# X14-Distribution.net
KiCad netlist of a schematic drawn in EAGLE
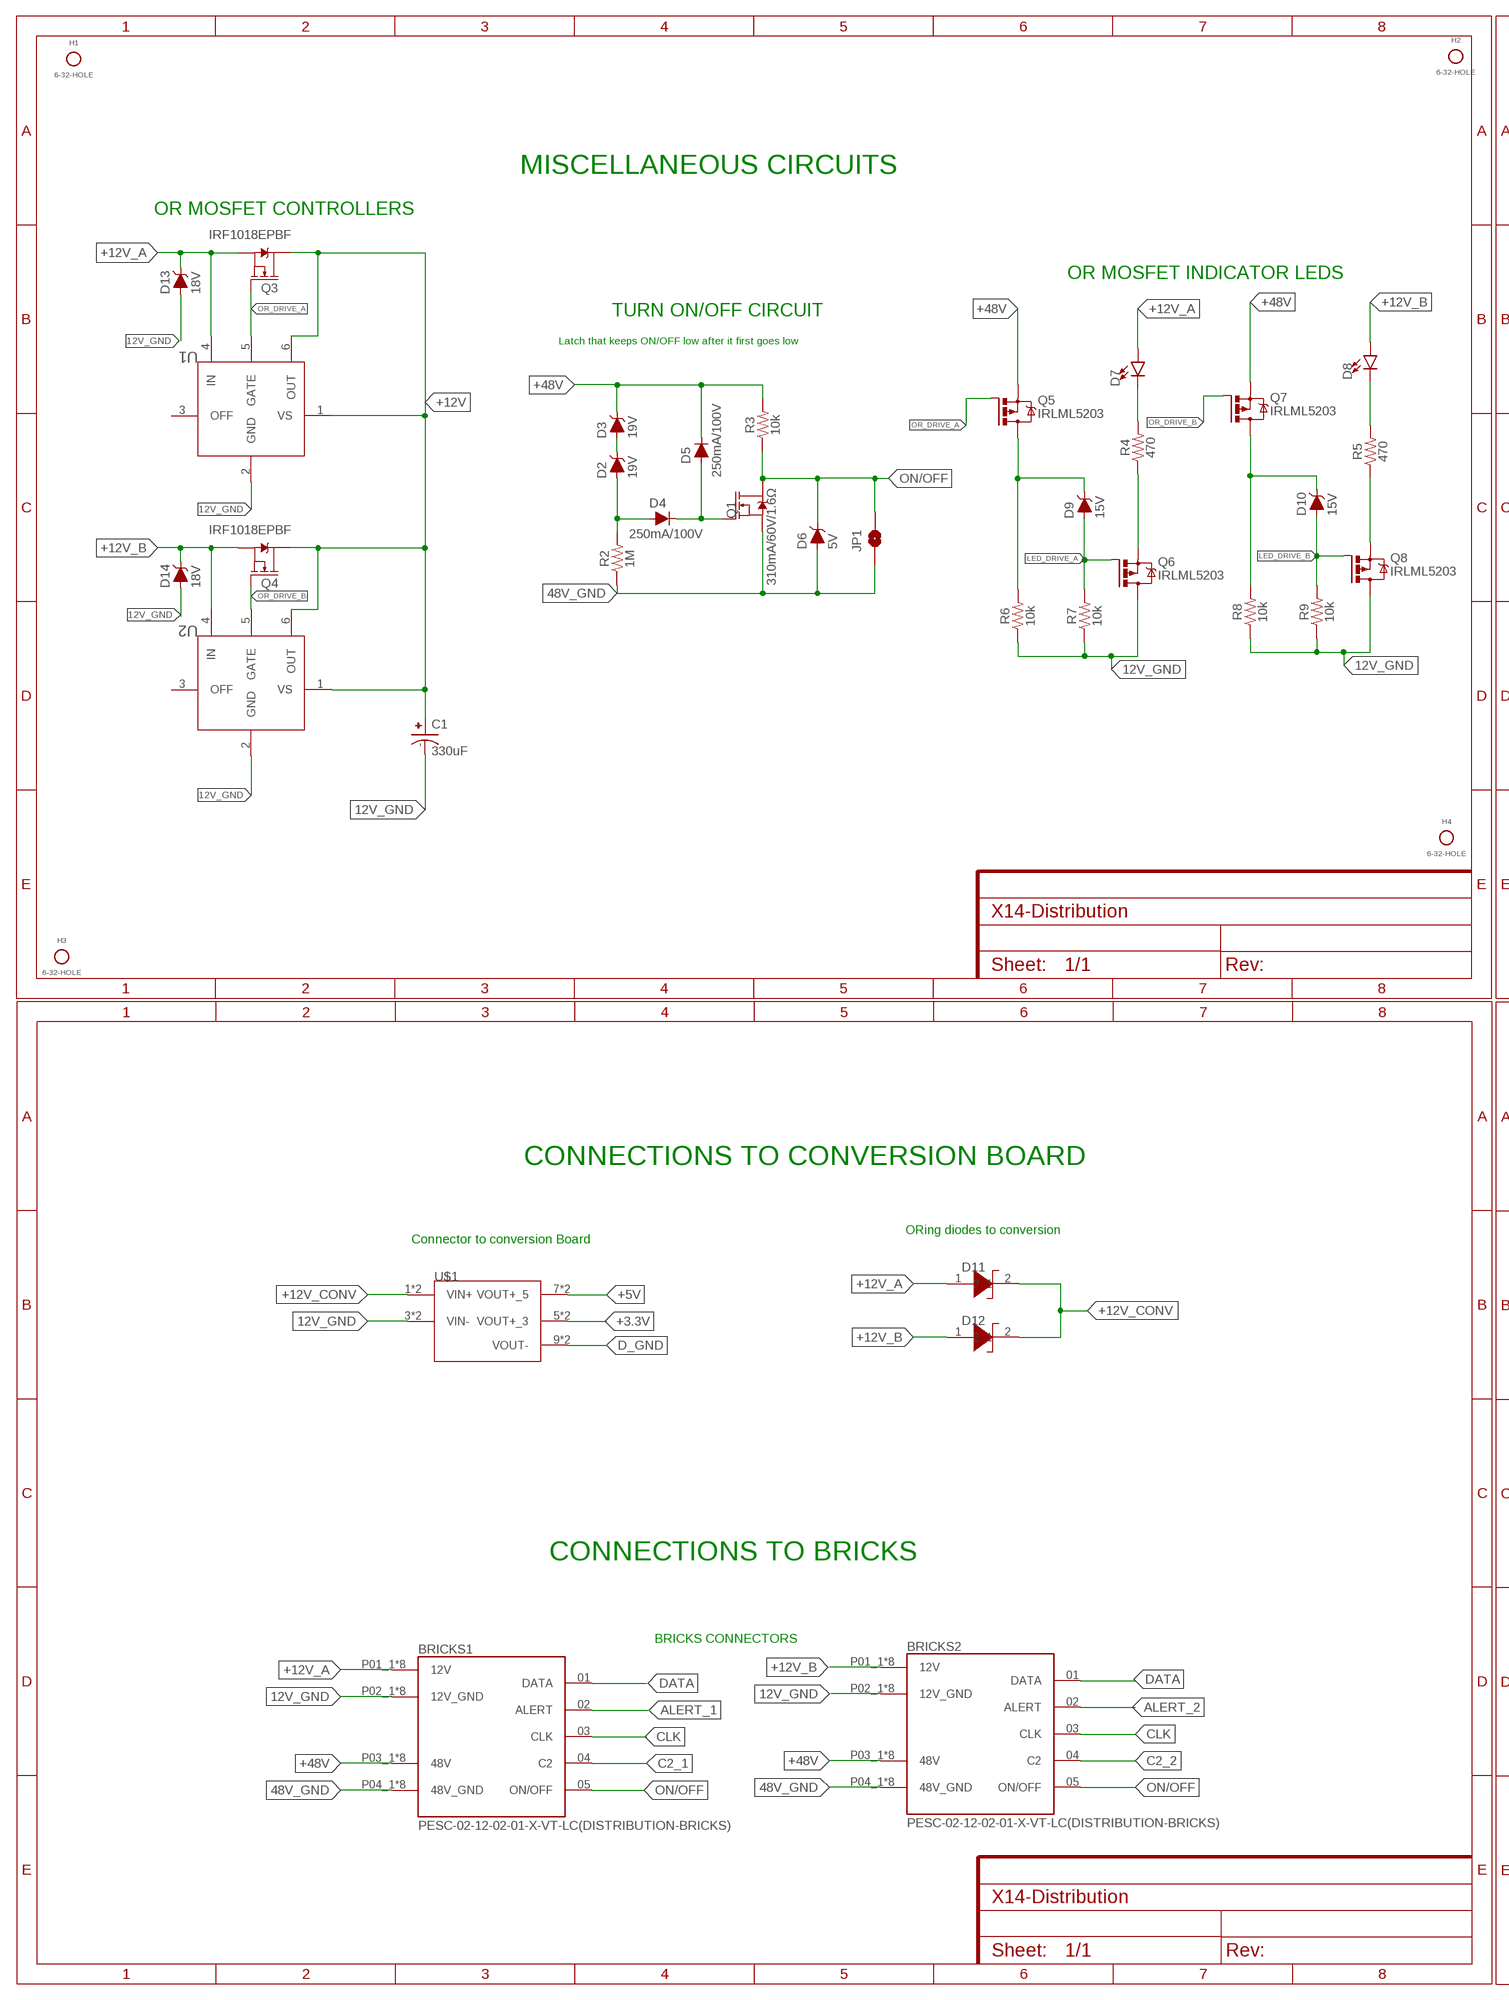
[diagram p0: schematic, sheet 1, part 1 of 2]
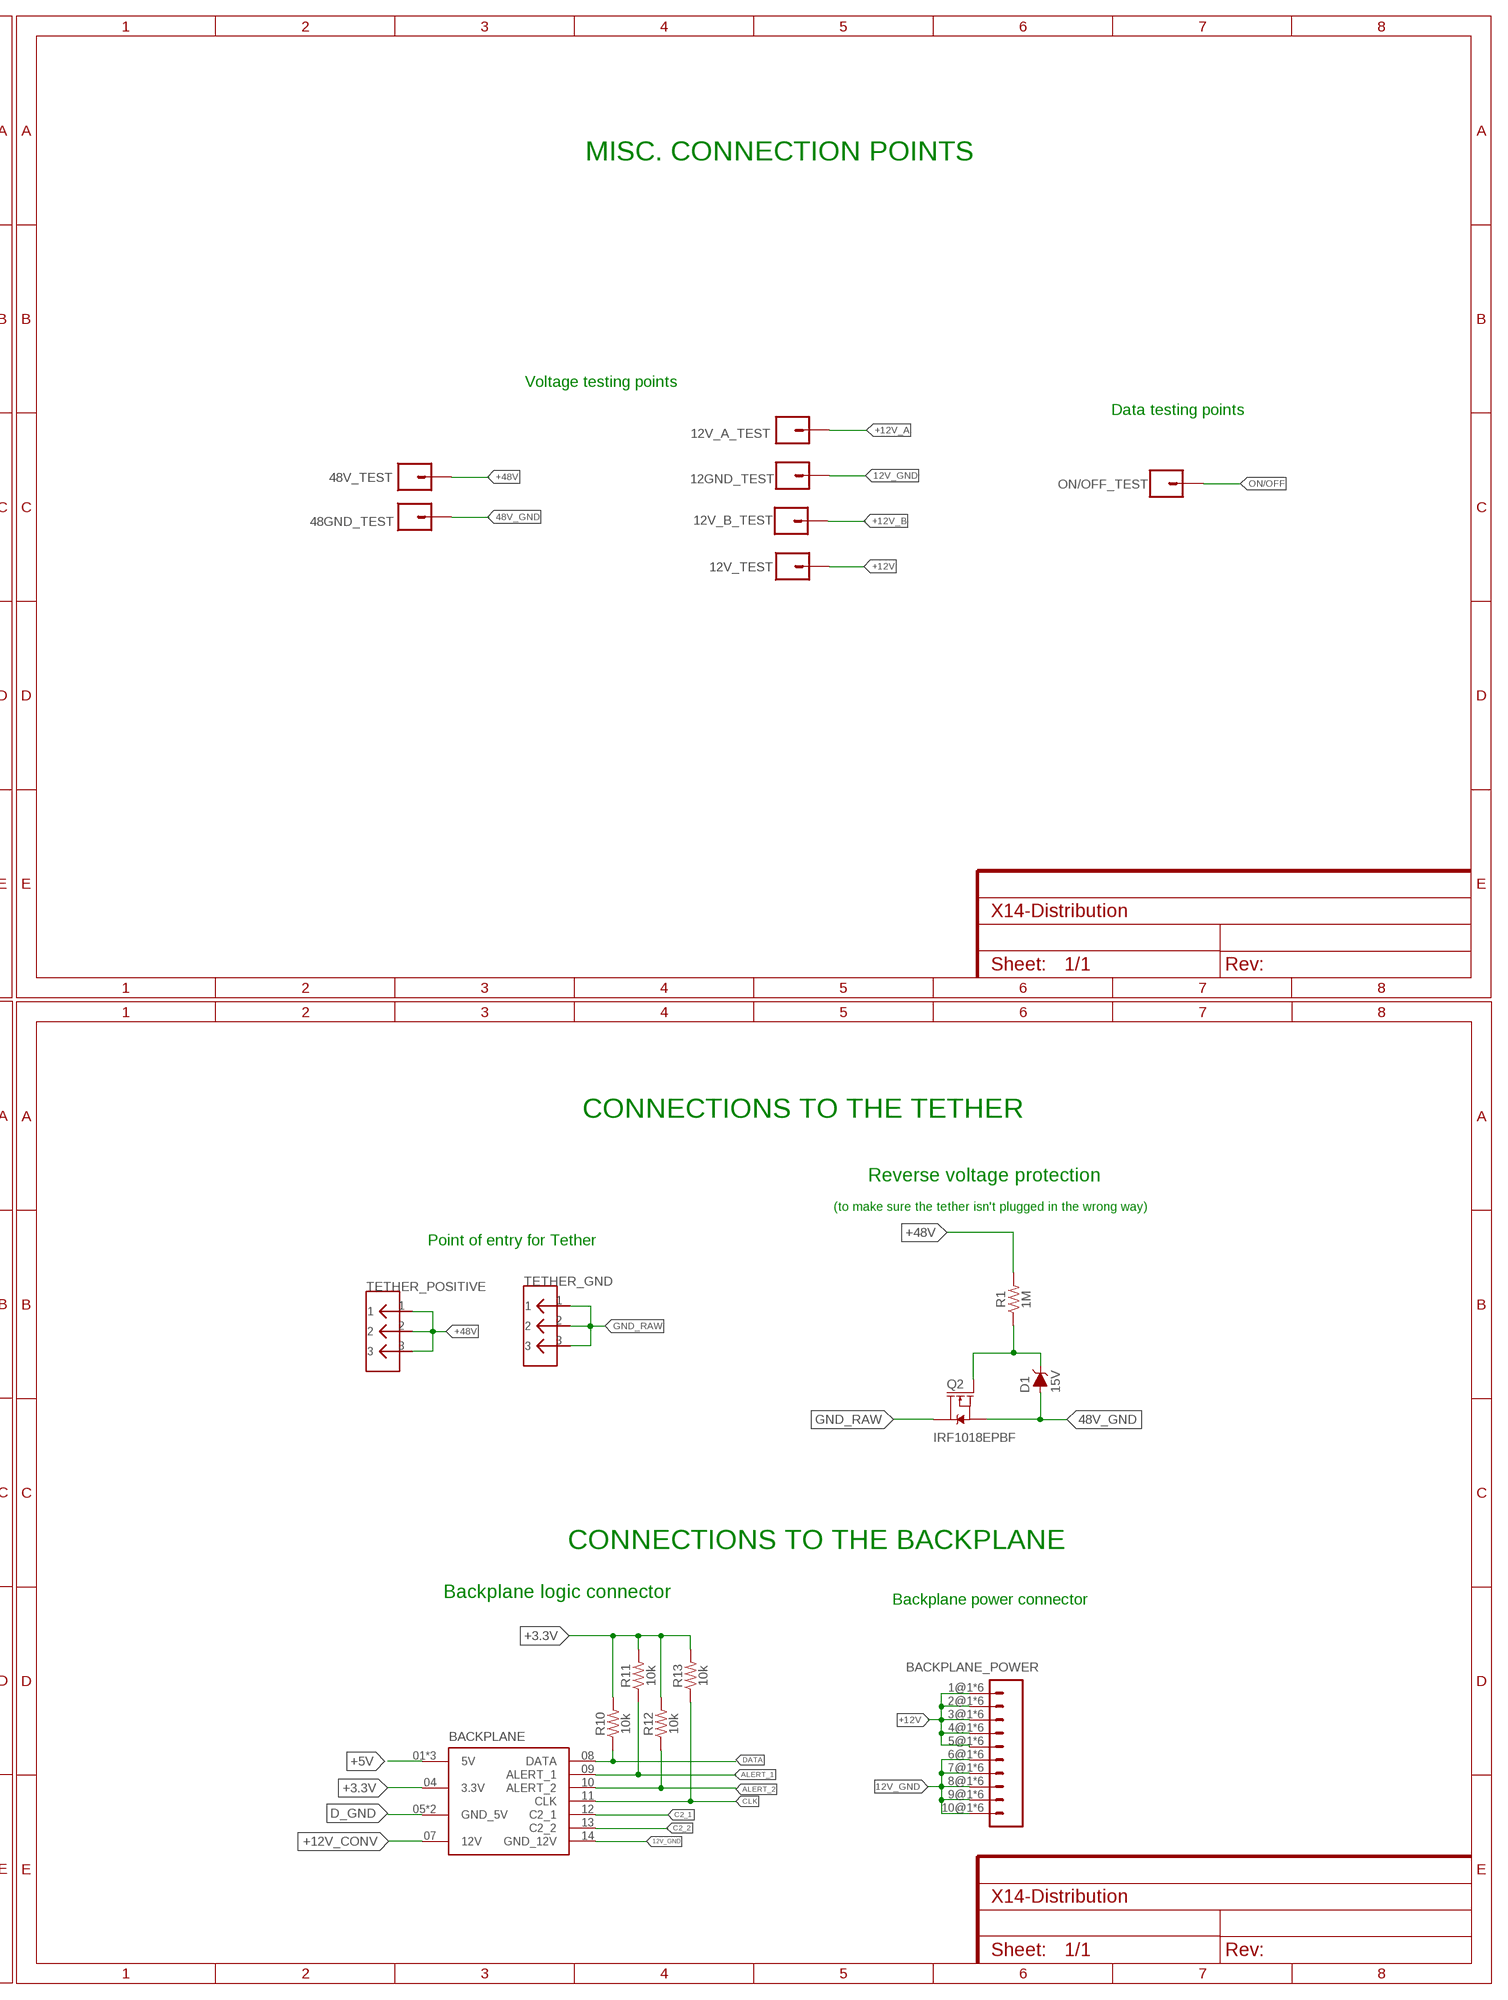
[diagram p1: schematic, sheet 1, part 2 of 2]

(export (version "E")
  (design (tool "Eeschema 10.0.6"))
  (components
    (comp (ref "12GND_TEST")
      (value "CONN_01")
      (footprint "eagle-import:1X01")
      (libsource (lib "eagle-import") (part "CONN_01"))
    )
    (comp (ref "12V_A_TEST")
      (value "CONN_01")
      (footprint "eagle-import:1X01")
      (libsource (lib "eagle-import") (part "CONN_01"))
    )
    (comp (ref "12V_B_TEST")
      (value "CONN_01")
      (footprint "eagle-import:1X01")
      (libsource (lib "eagle-import") (part "CONN_01"))
    )
    (comp (ref "12V_TEST")
      (value "CONN_01")
      (footprint "eagle-import:1X01")
      (libsource (lib "eagle-import") (part "CONN_01"))
    )
    (comp (ref "48GND_TEST")
      (value "CONN_01")
      (footprint "eagle-import:1X01")
      (libsource (lib "eagle-import") (part "CONN_01"))
    )
    (comp (ref "48V_TEST")
      (value "CONN_01")
      (footprint "eagle-import:1X01")
      (libsource (lib "eagle-import") (part "CONN_01"))
    )
    (comp (ref "BACKPLANE")
      (value "DISTRIBUTION-BACKPLANE")
      (footprint "eagle-import:SAMTEC_IPL1-107-01-X-D-K(D-B)")
      (libsource (lib "eagle-import") (part "DISTRIBUTION-BACKPLANE"))
    )
    (comp (ref "BACKPLANE_POWER")
      (value "MPPT-10-01-01-L-RA-SD")
      (footprint "eagle-import:MPPT-10-01-01-L-RA-SD")
      (libsource (lib "eagle-import") (part "MPPT-10-01-01-L-RA-SD"))
    )
    (comp (ref "BRICKS1")
      (value "PESC-02-12-02-01-X-VT-LC(DISTRIBUTION-BRICKS)")
      (footprint "eagle-import:SAMTEC_PESC-02-12-02-01-X-VT-LC(D-B)")
      (fields (field (name "MANUFACTURER") "Samtec"))
      (libsource (lib "eagle-import") (part "PESC-02-12-02-01-X-VT-LC(DISTRIBUTION-BRICKS)"))
    )
    (comp (ref "BRICKS2")
      (value "PESC-02-12-02-01-X-VT-LC(DISTRIBUTION-BRICKS)")
      (footprint "eagle-import:SAMTEC_PESC-02-12-02-01-X-VT-LC(D-B)")
      (fields (field (name "MANUFACTURER") "Samtec"))
      (libsource (lib "eagle-import") (part "PESC-02-12-02-01-X-VT-LC(DISTRIBUTION-BRICKS)"))
    )
    (comp (ref "C1")
      (value "330uF")
      (footprint "eagle-import:CAPAE1030X1050N")
      (fields
        (field (name "ARROW_PART_NUMBER") "UCM1H331MNL1GS")
        (field (name "MOUSER_PART_NUMBER") "647-UCM1H331MNL1GS")
      )
      (libsource (lib "eagle-import") (part "UCM1H331MNL1GS"))
    )
    (comp (ref "D1")
      (value "15V")
      (footprint "eagle-import:SOD-323")
      (libsource (lib "eagle-import") (part "DIODE-ZENER-BZT52C3V6S"))
    )
    (comp (ref "D2")
      (value "19V")
      (footprint "eagle-import:SOD-323")
      (libsource (lib "eagle-import") (part "DIODE-ZENER-BZT52C3V6S"))
    )
    (comp (ref "D3")
      (value "19V")
      (footprint "eagle-import:SOD-323")
      (libsource (lib "eagle-import") (part "DIODE-ZENER-BZT52C3V6S"))
    )
    (comp (ref "D4")
      (value "250mA/100V")
      (footprint "eagle-import:SOD-323")
      (libsource (lib "eagle-import") (part "DIODE-BAS16J"))
    )
    (comp (ref "D5")
      (value "250mA/100V")
      (footprint "eagle-import:SOD-323")
      (libsource (lib "eagle-import") (part "DIODE-BAS16J"))
    )
    (comp (ref "D6")
      (value "5V")
      (footprint "eagle-import:SOD-323")
      (libsource (lib "eagle-import") (part "DIODE-ZENER-BZT52C3V6S"))
    )
    (comp (ref "D7")
      (value "LED0603")
      (footprint "eagle-import:LED-0603")
      (libsource (lib "eagle-import") (part "LED0603"))
    )
    (comp (ref "D8")
      (value "LED0603")
      (footprint "eagle-import:LED-0603")
      (libsource (lib "eagle-import") (part "LED0603"))
    )
    (comp (ref "D9")
      (value "15V")
      (footprint "eagle-import:SOD-323")
      (libsource (lib "eagle-import") (part "DIODE-ZENER-BZT52C3V6S"))
    )
    (comp (ref "D10")
      (value "15V")
      (footprint "eagle-import:SOD-323")
      (libsource (lib "eagle-import") (part "DIODE-ZENER-BZT52C3V6S"))
    )
    (comp (ref "D11")
      (value "DIODE-DO-214AC(SK34ATR)")
      (footprint "eagle-import:DIODE-DO-214AC(SK34ATR)")
      (libsource (lib "eagle-import") (part "DIODE-DO-214AC(SK34ATR)"))
    )
    (comp (ref "D12")
      (value "DIODE-DO-214AC(SK34ATR)")
      (footprint "eagle-import:DIODE-DO-214AC(SK34ATR)")
      (libsource (lib "eagle-import") (part "DIODE-DO-214AC(SK34ATR)"))
    )
    (comp (ref "D13")
      (value "18V")
      (footprint "eagle-import:PANASONIC_SMINI2-F5-B")
      (libsource (lib "eagle-import") (part "DIODE-ZENER-DZ2J150M0L"))
    )
    (comp (ref "D14")
      (value "18V")
      (footprint "eagle-import:PANASONIC_SMINI2-F5-B")
      (libsource (lib "eagle-import") (part "DIODE-ZENER-DZ2J150M0L"))
    )
    (comp (ref "H1")
      (value "6-32-HOLE")
      (footprint "eagle-import:6-32-HOLE")
      (libsource (lib "eagle-import") (part "6-32-HOLE"))
    )
    (comp (ref "H2")
      (value "6-32-HOLE")
      (footprint "eagle-import:6-32-HOLE")
      (libsource (lib "eagle-import") (part "6-32-HOLE"))
    )
    (comp (ref "H3")
      (value "6-32-HOLE")
      (footprint "eagle-import:6-32-HOLE")
      (libsource (lib "eagle-import") (part "6-32-HOLE"))
    )
    (comp (ref "H4")
      (value "6-32-HOLE")
      (footprint "eagle-import:6-32-HOLE")
      (libsource (lib "eagle-import") (part "6-32-HOLE"))
    )
    (comp (ref "JP1")
      (value "JUMPER-SMT_2_NO_SILK")
      (footprint "eagle-import:SMT-JUMPER_2_NO_SILK")
      (libsource (lib "eagle-import") (part "JUMPER-SMT_2_NO_SILK"))
    )
    (comp (ref "ON/OFF_TEST")
      (value "CONN_01")
      (footprint "eagle-import:1X01")
      (libsource (lib "eagle-import") (part "CONN_01"))
    )
    (comp (ref "Q1")
      (value "310mA/60V/1.6Ω")
      (footprint "eagle-import:SOT323")
      (libsource (lib "eagle-import") (part "MOSFET-NCH-2N7002PW"))
    )
    (comp (ref "Q2")
      (value "IRF1018EPBF")
      (footprint "eagle-import:TO263")
      (libsource (lib "eagle-import") (part "IRF1018EPBF"))
    )
    (comp (ref "Q3")
      (value "IRF1018EPBF")
      (footprint "eagle-import:TO263")
      (libsource (lib "eagle-import") (part "IRF1018EPBF"))
    )
    (comp (ref "Q4")
      (value "IRF1018EPBF")
      (footprint "eagle-import:TO263")
      (libsource (lib "eagle-import") (part "IRF1018EPBF"))
    )
    (comp (ref "Q5")
      (value "IRLML5203")
      (footprint "eagle-import:SOT23")
      (fields (field (name "MANUFACTURER") "Infineon Technologies") (field (name "MPN") "IRLML5203TRPBF"))
      (libsource (lib "eagle-import") (part "PMOSFET_IRLML5203"))
    )
    (comp (ref "Q6")
      (value "IRLML5203")
      (footprint "eagle-import:SOT23")
      (fields (field (name "MANUFACTURER") "Infineon Technologies") (field (name "MPN") "IRLML5203TRPBF"))
      (libsource (lib "eagle-import") (part "PMOSFET_IRLML5203"))
    )
    (comp (ref "Q7")
      (value "IRLML5203")
      (footprint "eagle-import:SOT23")
      (fields (field (name "MANUFACTURER") "Infineon Technologies") (field (name "MPN") "IRLML5203TRPBF"))
      (libsource (lib "eagle-import") (part "PMOSFET_IRLML5203"))
    )
    (comp (ref "Q8")
      (value "IRLML5203")
      (footprint "eagle-import:SOT23")
      (fields (field (name "MANUFACTURER") "Infineon Technologies") (field (name "MPN") "IRLML5203TRPBF"))
      (libsource (lib "eagle-import") (part "PMOSFET_IRLML5203"))
    )
    (comp (ref "R1")
      (value "1M")
      (footprint "eagle-import:0603")
      (libsource (lib "eagle-import") (part "RESISTOR0603"))
    )
    (comp (ref "R2")
      (value "1M")
      (footprint "eagle-import:0603")
      (libsource (lib "eagle-import") (part "RESISTOR0603"))
    )
    (comp (ref "R3")
      (value "10k")
      (footprint "eagle-import:0603")
      (libsource (lib "eagle-import") (part "RESISTOR0603"))
    )
    (comp (ref "R4")
      (value "470")
      (footprint "eagle-import:0603")
      (libsource (lib "eagle-import") (part "RESISTOR0603"))
    )
    (comp (ref "R5")
      (value "470")
      (footprint "eagle-import:0603")
      (libsource (lib "eagle-import") (part "RESISTOR0603"))
    )
    (comp (ref "R6")
      (value "10k")
      (footprint "eagle-import:0603")
      (libsource (lib "eagle-import") (part "RESISTOR0603"))
    )
    (comp (ref "R7")
      (value "10k")
      (footprint "eagle-import:0603")
      (libsource (lib "eagle-import") (part "RESISTOR0603"))
    )
    (comp (ref "R8")
      (value "10k")
      (footprint "eagle-import:0603")
      (libsource (lib "eagle-import") (part "RESISTOR0603"))
    )
    (comp (ref "R9")
      (value "10k")
      (footprint "eagle-import:0603")
      (libsource (lib "eagle-import") (part "RESISTOR0603"))
    )
    (comp (ref "R10")
      (value "10k")
      (footprint "eagle-import:0603")
      (libsource (lib "eagle-import") (part "RESISTOR0603"))
    )
    (comp (ref "R11")
      (value "10k")
      (footprint "eagle-import:0603")
      (libsource (lib "eagle-import") (part "RESISTOR0603"))
    )
    (comp (ref "R12")
      (value "10k")
      (footprint "eagle-import:0603")
      (libsource (lib "eagle-import") (part "RESISTOR0603"))
    )
    (comp (ref "R13")
      (value "10k")
      (footprint "eagle-import:0603")
      (libsource (lib "eagle-import") (part "RESISTOR0603"))
    )
    (comp (ref "TETHER_GND")
      (value "796636-3")
      (footprint "eagle-import:796636-3")
      (libsource (lib "eagle-import") (part "796636-3"))
    )
    (comp (ref "TETHER_POSITIVE")
      (value "796636-3")
      (footprint "eagle-import:796636-3")
      (libsource (lib "eagle-import") (part "796636-3"))
    )
    (comp (ref "U$1")
      (value "DISTRIBUTION-CONVERSION")
      (footprint "eagle-import:TSW-105-05-G-S(D-C)")
      (libsource (lib "eagle-import") (part "DISTRIBUTION-CONVERSION"))
    )
    (comp (ref "U1")
      (value "DIST_OR_CONTROL_ALTMK06A-M")
      (footprint "eagle-import:SOT-23-6")
      (fields
        (field (name "MANUFACTURER") "Texas Instruments")
        (field (name "MANUFACTURER_PART_NUMBER") "LM5050MK-1/NOPB")
      )
      (libsource (lib "eagle-import") (part "DIST_OR_CONTROL_ALTMK06A-M"))
    )
    (comp (ref "U2")
      (value "DIST_OR_CONTROL_ALTMK06A-M")
      (footprint "eagle-import:SOT-23-6")
      (fields
        (field (name "MANUFACTURER") "Texas Instruments")
        (field (name "MANUFACTURER_PART_NUMBER") "LM5050MK-1/NOPB")
      )
      (libsource (lib "eagle-import") (part "DIST_OR_CONTROL_ALTMK06A-M"))
    )
  )
  (nets
    (net (code "1") (name "+3.3V") (class "Default")
      (node (ref "BACKPLANE") (pin "04") (pinfunction "3.3V_04") (pintype "passive"))
      (node (ref "R10") (pin "2") (pinfunction "2_2") (pintype "passive"))
      (node (ref "R11") (pin "2") (pinfunction "2_2") (pintype "passive"))
      (node (ref "R12") (pin "2") (pinfunction "2_2") (pintype "passive"))
      (node (ref "R13") (pin "2") (pinfunction "2_2") (pintype "passive"))
      (node (ref "U$1") (pin "5") (pinfunction "VOUT+_3_5") (pintype "bidirectional"))
      (node (ref "U$1") (pin "6") (pinfunction "VOUT+_3_6") (pintype "bidirectional"))
    )
    (net (code "2") (name "+5V") (class "Default")
      (node (ref "BACKPLANE") (pin "01") (pinfunction "5V_01") (pintype "passive"))
      (node (ref "BACKPLANE") (pin "02") (pinfunction "5V_02") (pintype "passive"))
      (node (ref "BACKPLANE") (pin "03") (pinfunction "5V_03") (pintype "passive"))
      (node (ref "U$1") (pin "7") (pinfunction "VOUT+_5_7") (pintype "bidirectional"))
      (node (ref "U$1") (pin "8") (pinfunction "VOUT+_5_8") (pintype "bidirectional"))
    )
    (net (code "3") (name "+12V") (class "Default")
      (node (ref "12V_TEST") (pin "1") (pinfunction "1_1") (pintype "passive"))
      (node (ref "BACKPLANE_POWER") (pin "1@1") (pinfunction "1_1@1") (pintype "passive"))
      (node (ref "BACKPLANE_POWER") (pin "1@2") (pinfunction "1_1@2") (pintype "passive"))
      (node (ref "BACKPLANE_POWER") (pin "1@3") (pinfunction "1_1@3") (pintype "passive"))
      (node (ref "BACKPLANE_POWER") (pin "1@4") (pinfunction "1_1@4") (pintype "passive"))
      (node (ref "BACKPLANE_POWER") (pin "1@5") (pinfunction "1_1@5") (pintype "passive"))
      (node (ref "BACKPLANE_POWER") (pin "1@6") (pinfunction "1_1@6") (pintype "passive"))
      (node (ref "BACKPLANE_POWER") (pin "2@1") (pinfunction "2_2@1") (pintype "passive"))
      (node (ref "BACKPLANE_POWER") (pin "2@2") (pinfunction "2_2@2") (pintype "passive"))
      (node (ref "BACKPLANE_POWER") (pin "2@3") (pinfunction "2_2@3") (pintype "passive"))
      (node (ref "BACKPLANE_POWER") (pin "2@4") (pinfunction "2_2@4") (pintype "passive"))
      (node (ref "BACKPLANE_POWER") (pin "2@5") (pinfunction "2_2@5") (pintype "passive"))
      (node (ref "BACKPLANE_POWER") (pin "2@6") (pinfunction "2_2@6") (pintype "passive"))
      (node (ref "BACKPLANE_POWER") (pin "3@1") (pinfunction "3_3@1") (pintype "passive"))
      (node (ref "BACKPLANE_POWER") (pin "3@2") (pinfunction "3_3@2") (pintype "passive"))
      (node (ref "BACKPLANE_POWER") (pin "3@3") (pinfunction "3_3@3") (pintype "passive"))
      (node (ref "BACKPLANE_POWER") (pin "3@4") (pinfunction "3_3@4") (pintype "passive"))
      (node (ref "BACKPLANE_POWER") (pin "3@5") (pinfunction "3_3@5") (pintype "passive"))
      (node (ref "BACKPLANE_POWER") (pin "3@6") (pinfunction "3_3@6") (pintype "passive"))
      (node (ref "BACKPLANE_POWER") (pin "4@1") (pinfunction "4_4@1") (pintype "passive"))
      (node (ref "BACKPLANE_POWER") (pin "4@2") (pinfunction "4_4@2") (pintype "passive"))
      (node (ref "BACKPLANE_POWER") (pin "4@3") (pinfunction "4_4@3") (pintype "passive"))
      (node (ref "BACKPLANE_POWER") (pin "4@4") (pinfunction "4_4@4") (pintype "passive"))
      (node (ref "BACKPLANE_POWER") (pin "4@5") (pinfunction "4_4@5") (pintype "passive"))
      (node (ref "BACKPLANE_POWER") (pin "4@6") (pinfunction "4_4@6") (pintype "passive"))
      (node (ref "BACKPLANE_POWER") (pin "5@1") (pinfunction "5_5@1") (pintype "passive"))
      (node (ref "BACKPLANE_POWER") (pin "5@2") (pinfunction "5_5@2") (pintype "passive"))
      (node (ref "BACKPLANE_POWER") (pin "5@3") (pinfunction "5_5@3") (pintype "passive"))
      (node (ref "BACKPLANE_POWER") (pin "5@4") (pinfunction "5_5@4") (pintype "passive"))
      (node (ref "BACKPLANE_POWER") (pin "5@5") (pinfunction "5_5@5") (pintype "passive"))
      (node (ref "BACKPLANE_POWER") (pin "5@6") (pinfunction "5_5@6") (pintype "passive"))
      (node (ref "C1") (pin "+") (pinfunction "+_+") (pintype "bidirectional"))
      (node (ref "Q3") (pin "3") (pinfunction "D_3") (pintype "bidirectional"))
      (node (ref "Q4") (pin "3") (pinfunction "D_3") (pintype "bidirectional"))
      (node (ref "U1") (pin "1") (pinfunction "VS_1") (pintype "passive"))
      (node (ref "U1") (pin "6") (pinfunction "OUT_6") (pintype "output"))
      (node (ref "U2") (pin "1") (pinfunction "VS_1") (pintype "passive"))
      (node (ref "U2") (pin "6") (pinfunction "OUT_6") (pintype "output"))
    )
    (net (code "4") (name "+12V_A") (class "Default")
      (node (ref "12V_A_TEST") (pin "1") (pinfunction "1_1") (pintype "passive"))
      (node (ref "BRICKS1") (pin "P01_1") (pinfunction "12V_P01_1") (pintype "power_in"))
      (node (ref "BRICKS1") (pin "P01_2") (pinfunction "12V_P01_2") (pintype "power_in"))
      (node (ref "BRICKS1") (pin "P01_3") (pinfunction "12V_P01_3") (pintype "power_in"))
      (node (ref "BRICKS1") (pin "P01_4") (pinfunction "12V_P01_4") (pintype "power_in"))
      (node (ref "BRICKS1") (pin "P01_5") (pinfunction "12V_P01_5") (pintype "power_in"))
      (node (ref "BRICKS1") (pin "P01_6") (pinfunction "12V_P01_6") (pintype "power_in"))
      (node (ref "BRICKS1") (pin "P01_7") (pinfunction "12V_P01_7") (pintype "power_in"))
      (node (ref "BRICKS1") (pin "P01_8") (pinfunction "12V_P01_8") (pintype "power_in"))
      (node (ref "D11") (pin "1") (pinfunction "1_1") (pintype "bidirectional"))
      (node (ref "D13") (pin "C") (pinfunction "C_C") (pintype "passive"))
      (node (ref "D7") (pin "A") (pinfunction "A_A") (pintype "passive"))
      (node (ref "Q3") (pin "2") (pinfunction "S_2") (pintype "bidirectional"))
      (node (ref "U1") (pin "4") (pinfunction "IN_4") (pintype "input"))
    )
    (net (code "5") (name "+12V_B") (class "Default")
      (node (ref "12V_B_TEST") (pin "1") (pinfunction "1_1") (pintype "passive"))
      (node (ref "BRICKS2") (pin "P01_1") (pinfunction "12V_P01_1") (pintype "power_in"))
      (node (ref "BRICKS2") (pin "P01_2") (pinfunction "12V_P01_2") (pintype "power_in"))
      (node (ref "BRICKS2") (pin "P01_3") (pinfunction "12V_P01_3") (pintype "power_in"))
      (node (ref "BRICKS2") (pin "P01_4") (pinfunction "12V_P01_4") (pintype "power_in"))
      (node (ref "BRICKS2") (pin "P01_5") (pinfunction "12V_P01_5") (pintype "power_in"))
      (node (ref "BRICKS2") (pin "P01_6") (pinfunction "12V_P01_6") (pintype "power_in"))
      (node (ref "BRICKS2") (pin "P01_7") (pinfunction "12V_P01_7") (pintype "power_in"))
      (node (ref "BRICKS2") (pin "P01_8") (pinfunction "12V_P01_8") (pintype "power_in"))
      (node (ref "D12") (pin "1") (pinfunction "1_1") (pintype "bidirectional"))
      (node (ref "D14") (pin "C") (pinfunction "C_C") (pintype "passive"))
      (node (ref "D8") (pin "A") (pinfunction "A_A") (pintype "passive"))
      (node (ref "Q4") (pin "2") (pinfunction "S_2") (pintype "bidirectional"))
      (node (ref "U2") (pin "4") (pinfunction "IN_4") (pintype "input"))
    )
    (net (code "6") (name "+12V_CONV") (class "Default")
      (node (ref "BACKPLANE") (pin "07") (pinfunction "12V_07") (pintype "passive"))
      (node (ref "D11") (pin "2") (pinfunction "2_2") (pintype "bidirectional"))
      (node (ref "D12") (pin "2") (pinfunction "2_2") (pintype "bidirectional"))
      (node (ref "U$1") (pin "1") (pinfunction "VIN+_1") (pintype "bidirectional"))
      (node (ref "U$1") (pin "2") (pinfunction "VIN+_2") (pintype "bidirectional"))
    )
    (net (code "7") (name "+48V") (class "Default")
      (node (ref "48V_TEST") (pin "1") (pinfunction "1_1") (pintype "passive"))
      (node (ref "BRICKS1") (pin "P03_1") (pinfunction "48V_P03_1") (pintype "power_in"))
      (node (ref "BRICKS1") (pin "P03_2") (pinfunction "48V_P03_2") (pintype "power_in"))
      (node (ref "BRICKS1") (pin "P03_3") (pinfunction "48V_P03_3") (pintype "power_in"))
      (node (ref "BRICKS1") (pin "P03_4") (pinfunction "48V_P03_4") (pintype "power_in"))
      (node (ref "BRICKS1") (pin "P03_5") (pinfunction "48V_P03_5") (pintype "power_in"))
      (node (ref "BRICKS1") (pin "P03_6") (pinfunction "48V_P03_6") (pintype "power_in"))
      (node (ref "BRICKS1") (pin "P03_7") (pinfunction "48V_P03_7") (pintype "power_in"))
      (node (ref "BRICKS1") (pin "P03_8") (pinfunction "48V_P03_8") (pintype "power_in"))
      (node (ref "BRICKS2") (pin "P03_1") (pinfunction "48V_P03_1") (pintype "power_in"))
      (node (ref "BRICKS2") (pin "P03_2") (pinfunction "48V_P03_2") (pintype "power_in"))
      (node (ref "BRICKS2") (pin "P03_3") (pinfunction "48V_P03_3") (pintype "power_in"))
      (node (ref "BRICKS2") (pin "P03_4") (pinfunction "48V_P03_4") (pintype "power_in"))
      (node (ref "BRICKS2") (pin "P03_5") (pinfunction "48V_P03_5") (pintype "power_in"))
      (node (ref "BRICKS2") (pin "P03_6") (pinfunction "48V_P03_6") (pintype "power_in"))
      (node (ref "BRICKS2") (pin "P03_7") (pinfunction "48V_P03_7") (pintype "power_in"))
      (node (ref "BRICKS2") (pin "P03_8") (pinfunction "48V_P03_8") (pintype "power_in"))
      (node (ref "D3") (pin "C") (pinfunction "C_C") (pintype "passive"))
      (node (ref "D5") (pin "C") (pinfunction "C_C") (pintype "passive"))
      (node (ref "Q5") (pin "2") (pinfunction "S_2") (pintype "passive"))
      (node (ref "Q7") (pin "2") (pinfunction "S_2") (pintype "passive"))
      (node (ref "R1") (pin "2") (pinfunction "2_2") (pintype "passive"))
      (node (ref "R3") (pin "2") (pinfunction "2_2") (pintype "passive"))
      (node (ref "TETHER_POSITIVE") (pin "1") (pinfunction "1_1") (pintype "bidirectional"))
      (node (ref "TETHER_POSITIVE") (pin "2") (pinfunction "2_2") (pintype "bidirectional"))
      (node (ref "TETHER_POSITIVE") (pin "3") (pinfunction "3_3") (pintype "bidirectional"))
    )
    (net (code "8") (name "12V_GND") (class "Default")
      (node (ref "12GND_TEST") (pin "1") (pinfunction "1_1") (pintype "passive"))
      (node (ref "BACKPLANE") (pin "14") (pinfunction "GND_12V_14") (pintype "passive"))
      (node (ref "BACKPLANE_POWER") (pin "10@1") (pinfunction "10_10@1") (pintype "passive"))
      (node (ref "BACKPLANE_POWER") (pin "10@2") (pinfunction "10_10@2") (pintype "passive"))
      (node (ref "BACKPLANE_POWER") (pin "10@3") (pinfunction "10_10@3") (pintype "passive"))
      (node (ref "BACKPLANE_POWER") (pin "10@4") (pinfunction "10_10@4") (pintype "passive"))
      (node (ref "BACKPLANE_POWER") (pin "10@5") (pinfunction "10_10@5") (pintype "passive"))
      (node (ref "BACKPLANE_POWER") (pin "10@6") (pinfunction "10_10@6") (pintype "passive"))
      (node (ref "BACKPLANE_POWER") (pin "6@1") (pinfunction "6_6@1") (pintype "passive"))
      (node (ref "BACKPLANE_POWER") (pin "6@2") (pinfunction "6_6@2") (pintype "passive"))
      (node (ref "BACKPLANE_POWER") (pin "6@3") (pinfunction "6_6@3") (pintype "passive"))
      (node (ref "BACKPLANE_POWER") (pin "6@4") (pinfunction "6_6@4") (pintype "passive"))
      (node (ref "BACKPLANE_POWER") (pin "6@5") (pinfunction "6_6@5") (pintype "passive"))
      (node (ref "BACKPLANE_POWER") (pin "6@6") (pinfunction "6_6@6") (pintype "passive"))
      (node (ref "BACKPLANE_POWER") (pin "7@1") (pinfunction "7_7@1") (pintype "passive"))
      (node (ref "BACKPLANE_POWER") (pin "7@2") (pinfunction "7_7@2") (pintype "passive"))
      (node (ref "BACKPLANE_POWER") (pin "7@3") (pinfunction "7_7@3") (pintype "passive"))
      (node (ref "BACKPLANE_POWER") (pin "7@4") (pinfunction "7_7@4") (pintype "passive"))
      (node (ref "BACKPLANE_POWER") (pin "7@5") (pinfunction "7_7@5") (pintype "passive"))
      (node (ref "BACKPLANE_POWER") (pin "7@6") (pinfunction "7_7@6") (pintype "passive"))
      (node (ref "BACKPLANE_POWER") (pin "8@1") (pinfunction "8_8@1") (pintype "passive"))
      (node (ref "BACKPLANE_POWER") (pin "8@2") (pinfunction "8_8@2") (pintype "passive"))
      (node (ref "BACKPLANE_POWER") (pin "8@3") (pinfunction "8_8@3") (pintype "passive"))
      (node (ref "BACKPLANE_POWER") (pin "8@4") (pinfunction "8_8@4") (pintype "passive"))
      (node (ref "BACKPLANE_POWER") (pin "8@5") (pinfunction "8_8@5") (pintype "passive"))
      (node (ref "BACKPLANE_POWER") (pin "8@6") (pinfunction "8_8@6") (pintype "passive"))
      (node (ref "BACKPLANE_POWER") (pin "9@1") (pinfunction "9_9@1") (pintype "passive"))
      (node (ref "BACKPLANE_POWER") (pin "9@2") (pinfunction "9_9@2") (pintype "passive"))
      (node (ref "BACKPLANE_POWER") (pin "9@3") (pinfunction "9_9@3") (pintype "passive"))
      (node (ref "BACKPLANE_POWER") (pin "9@4") (pinfunction "9_9@4") (pintype "passive"))
      (node (ref "BACKPLANE_POWER") (pin "9@5") (pinfunction "9_9@5") (pintype "passive"))
      (node (ref "BACKPLANE_POWER") (pin "9@6") (pinfunction "9_9@6") (pintype "passive"))
      (node (ref "BRICKS1") (pin "P02_1") (pinfunction "12V_GND_P02_1") (pintype "power_in"))
      (node (ref "BRICKS1") (pin "P02_2") (pinfunction "12V_GND_P02_2") (pintype "power_in"))
      (node (ref "BRICKS1") (pin "P02_3") (pinfunction "12V_GND_P02_3") (pintype "power_in"))
      (node (ref "BRICKS1") (pin "P02_4") (pinfunction "12V_GND_P02_4") (pintype "power_in"))
      (node (ref "BRICKS1") (pin "P02_5") (pinfunction "12V_GND_P02_5") (pintype "power_in"))
      (node (ref "BRICKS1") (pin "P02_6") (pinfunction "12V_GND_P02_6") (pintype "power_in"))
      (node (ref "BRICKS1") (pin "P02_7") (pinfunction "12V_GND_P02_7") (pintype "power_in"))
      (node (ref "BRICKS1") (pin "P02_8") (pinfunction "12V_GND_P02_8") (pintype "power_in"))
      (node (ref "BRICKS2") (pin "P02_1") (pinfunction "12V_GND_P02_1") (pintype "power_in"))
      (node (ref "BRICKS2") (pin "P02_2") (pinfunction "12V_GND_P02_2") (pintype "power_in"))
      (node (ref "BRICKS2") (pin "P02_3") (pinfunction "12V_GND_P02_3") (pintype "power_in"))
      (node (ref "BRICKS2") (pin "P02_4") (pinfunction "12V_GND_P02_4") (pintype "power_in"))
      (node (ref "BRICKS2") (pin "P02_5") (pinfunction "12V_GND_P02_5") (pintype "power_in"))
      (node (ref "BRICKS2") (pin "P02_6") (pinfunction "12V_GND_P02_6") (pintype "power_in"))
      (node (ref "BRICKS2") (pin "P02_7") (pinfunction "12V_GND_P02_7") (pintype "power_in"))
      (node (ref "BRICKS2") (pin "P02_8") (pinfunction "12V_GND_P02_8") (pintype "power_in"))
      (node (ref "C1") (pin "-") (pinfunction "-_-") (pintype "bidirectional"))
      (node (ref "D13") (pin "A") (pinfunction "A_A") (pintype "passive"))
      (node (ref "D14") (pin "A") (pinfunction "A_A") (pintype "passive"))
      (node (ref "Q6") (pin "3") (pinfunction "D_3") (pintype "passive"))
      (node (ref "Q8") (pin "3") (pinfunction "D_3") (pintype "passive"))
      (node (ref "R6") (pin "1") (pinfunction "1_1") (pintype "passive"))
      (node (ref "R7") (pin "1") (pinfunction "1_1") (pintype "passive"))
      (node (ref "R8") (pin "1") (pinfunction "1_1") (pintype "passive"))
      (node (ref "R9") (pin "1") (pinfunction "1_1") (pintype "passive"))
      (node (ref "U$1") (pin "3") (pinfunction "VIN-_3") (pintype "bidirectional"))
      (node (ref "U$1") (pin "4") (pinfunction "VIN-_4") (pintype "bidirectional"))
      (node (ref "U1") (pin "2") (pinfunction "GND_2") (pintype "power_in"))
      (node (ref "U2") (pin "2") (pinfunction "GND_2") (pintype "power_in"))
    )
    (net (code "9") (name "48V_GND") (class "Default")
      (node (ref "48GND_TEST") (pin "1") (pinfunction "1_1") (pintype "passive"))
      (node (ref "BRICKS1") (pin "P04_1") (pinfunction "48V_GND_P04_1") (pintype "power_in"))
      (node (ref "BRICKS1") (pin "P04_2") (pinfunction "48V_GND_P04_2") (pintype "power_in"))
      (node (ref "BRICKS1") (pin "P04_3") (pinfunction "48V_GND_P04_3") (pintype "power_in"))
      (node (ref "BRICKS1") (pin "P04_4") (pinfunction "48V_GND_P04_4") (pintype "power_in"))
      (node (ref "BRICKS1") (pin "P04_5") (pinfunction "48V_GND_P04_5") (pintype "power_in"))
      (node (ref "BRICKS1") (pin "P04_6") (pinfunction "48V_GND_P04_6") (pintype "power_in"))
      (node (ref "BRICKS1") (pin "P04_7") (pinfunction "48V_GND_P04_7") (pintype "power_in"))
      (node (ref "BRICKS1") (pin "P04_8") (pinfunction "48V_GND_P04_8") (pintype "power_in"))
      (node (ref "BRICKS2") (pin "P04_1") (pinfunction "48V_GND_P04_1") (pintype "power_in"))
      (node (ref "BRICKS2") (pin "P04_2") (pinfunction "48V_GND_P04_2") (pintype "power_in"))
      (node (ref "BRICKS2") (pin "P04_3") (pinfunction "48V_GND_P04_3") (pintype "power_in"))
      (node (ref "BRICKS2") (pin "P04_4") (pinfunction "48V_GND_P04_4") (pintype "power_in"))
      (node (ref "BRICKS2") (pin "P04_5") (pinfunction "48V_GND_P04_5") (pintype "power_in"))
      (node (ref "BRICKS2") (pin "P04_6") (pinfunction "48V_GND_P04_6") (pintype "power_in"))
      (node (ref "BRICKS2") (pin "P04_7") (pinfunction "48V_GND_P04_7") (pintype "power_in"))
      (node (ref "BRICKS2") (pin "P04_8") (pinfunction "48V_GND_P04_8") (pintype "power_in"))
      (node (ref "D1") (pin "A") (pinfunction "A_A") (pintype "passive"))
      (node (ref "D6") (pin "A") (pinfunction "A_A") (pintype "passive"))
      (node (ref "JP1") (pin "1") (pinfunction "1_1") (pintype "passive"))
      (node (ref "Q1") (pin "2") (pinfunction "S_2") (pintype "bidirectional"))
      (node (ref "Q2") (pin "2") (pinfunction "S_2") (pintype "bidirectional"))
      (node (ref "R2") (pin "1") (pinfunction "1_1") (pintype "passive"))
    )
    (net (code "10") (name "ALERT_1") (class "Default")
      (node (ref "BACKPLANE") (pin "09") (pinfunction "ALERT_1_09") (pintype "passive"))
      (node (ref "BRICKS1") (pin "02") (pinfunction "ALERT_02") (pintype "passive"))
      (node (ref "R11") (pin "1") (pinfunction "1_1") (pintype "passive"))
    )
    (net (code "11") (name "ALERT_2") (class "Default")
      (node (ref "BACKPLANE") (pin "10") (pinfunction "ALERT_2_10") (pintype "passive"))
      (node (ref "BRICKS2") (pin "02") (pinfunction "ALERT_02") (pintype "passive"))
      (node (ref "R12") (pin "1") (pinfunction "1_1") (pintype "passive"))
    )
    (net (code "12") (name "C2_1") (class "Default")
      (node (ref "BACKPLANE") (pin "12") (pinfunction "C2_1_12") (pintype "passive"))
      (node (ref "BRICKS1") (pin "04") (pinfunction "C2_04") (pintype "passive"))
    )
    (net (code "13") (name "C2_2") (class "Default")
      (node (ref "BACKPLANE") (pin "13") (pinfunction "C2_2_13") (pintype "passive"))
      (node (ref "BRICKS2") (pin "04") (pinfunction "C2_04") (pintype "passive"))
    )
    (net (code "14") (name "CLK") (class "Default")
      (node (ref "BACKPLANE") (pin "11") (pinfunction "CLK_11") (pintype "passive"))
      (node (ref "BRICKS1") (pin "03") (pinfunction "CLK_03") (pintype "passive"))
      (node (ref "BRICKS2") (pin "03") (pinfunction "CLK_03") (pintype "passive"))
      (node (ref "R13") (pin "1") (pinfunction "1_1") (pintype "passive"))
    )
    (net (code "15") (name "DATA") (class "Default")
      (node (ref "BACKPLANE") (pin "08") (pinfunction "DATA_08") (pintype "passive"))
      (node (ref "BRICKS1") (pin "01") (pinfunction "DATA_01") (pintype "passive"))
      (node (ref "BRICKS2") (pin "01") (pinfunction "DATA_01") (pintype "passive"))
      (node (ref "R10") (pin "1") (pinfunction "1_1") (pintype "passive"))
    )
    (net (code "16") (name "D_GND") (class "Default")
      (node (ref "BACKPLANE") (pin "05") (pinfunction "GND_5V_05") (pintype "passive"))
      (node (ref "BACKPLANE") (pin "06") (pinfunction "GND_5V_06") (pintype "passive"))
      (node (ref "U$1") (pin "10") (pinfunction "VOUT-_10") (pintype "bidirectional"))
      (node (ref "U$1") (pin "9") (pinfunction "VOUT-_9") (pintype "bidirectional"))
    )
    (net (code "17") (name "GND_RAW") (class "Default")
      (node (ref "Q2") (pin "3") (pinfunction "D_3") (pintype "bidirectional"))
      (node (ref "TETHER_GND") (pin "1") (pinfunction "1_1") (pintype "bidirectional"))
      (node (ref "TETHER_GND") (pin "2") (pinfunction "2_2") (pintype "bidirectional"))
      (node (ref "TETHER_GND") (pin "3") (pinfunction "3_3") (pintype "bidirectional"))
    )
    (net (code "18") (name "LED_DRIVE_A") (class "Default")
      (node (ref "D9") (pin "A") (pinfunction "A_A") (pintype "passive"))
      (node (ref "Q6") (pin "1") (pinfunction "G_1") (pintype "passive"))
      (node (ref "R7") (pin "2") (pinfunction "2_2") (pintype "passive"))
    )
    (net (code "19") (name "LED_DRIVE_B") (class "Default")
      (node (ref "D10") (pin "A") (pinfunction "A_A") (pintype "passive"))
      (node (ref "Q8") (pin "1") (pinfunction "G_1") (pintype "passive"))
      (node (ref "R9") (pin "2") (pinfunction "2_2") (pintype "passive"))
    )
    (net (code "20") (name "Net-(D2-PadA)") (class "Default")
      (node (ref "D2") (pin "A") (pinfunction "A_A") (pintype "passive"))
      (node (ref "D4") (pin "A") (pinfunction "A_A") (pintype "passive"))
      (node (ref "R2") (pin "2") (pinfunction "2_2") (pintype "passive"))
    )
    (net (code "21") (name "Net-(D2-PadC)") (class "Default")
      (node (ref "D2") (pin "C") (pinfunction "C_C") (pintype "passive"))
      (node (ref "D3") (pin "A") (pinfunction "A_A") (pintype "passive"))
    )
    (net (code "22") (name "Net-(D7-PadC)") (class "Default")
      (node (ref "D7") (pin "C") (pinfunction "C_C") (pintype "passive"))
      (node (ref "R4") (pin "2") (pinfunction "2_2") (pintype "passive"))
    )
    (net (code "23") (name "Net-(D8-PadC)") (class "Default")
      (node (ref "D8") (pin "C") (pinfunction "C_C") (pintype "passive"))
      (node (ref "R5") (pin "2") (pinfunction "2_2") (pintype "passive"))
    )
    (net (code "24") (name "Net-(Q1-G)") (class "Default")
      (node (ref "D4") (pin "C") (pinfunction "C_C") (pintype "passive"))
      (node (ref "D5") (pin "A") (pinfunction "A_A") (pintype "passive"))
      (node (ref "Q1") (pin "1") (pinfunction "G_1") (pintype "bidirectional"))
    )
    (net (code "25") (name "Net-(Q2-G)") (class "Default")
      (node (ref "D1") (pin "C") (pinfunction "C_C") (pintype "passive"))
      (node (ref "Q2") (pin "1") (pinfunction "G_1") (pintype "bidirectional"))
      (node (ref "R1") (pin "1") (pinfunction "1_1") (pintype "passive"))
    )
    (net (code "26") (name "Net-(Q5-D)") (class "Default")
      (node (ref "D9") (pin "C") (pinfunction "C_C") (pintype "passive"))
      (node (ref "Q5") (pin "3") (pinfunction "D_3") (pintype "passive"))
      (node (ref "R6") (pin "2") (pinfunction "2_2") (pintype "passive"))
    )
    (net (code "27") (name "Net-(Q6-S)") (class "Default")
      (node (ref "Q6") (pin "2") (pinfunction "S_2") (pintype "passive"))
      (node (ref "R4") (pin "1") (pinfunction "1_1") (pintype "passive"))
    )
    (net (code "28") (name "Net-(Q7-D)") (class "Default")
      (node (ref "D10") (pin "C") (pinfunction "C_C") (pintype "passive"))
      (node (ref "Q7") (pin "3") (pinfunction "D_3") (pintype "passive"))
      (node (ref "R8") (pin "2") (pinfunction "2_2") (pintype "passive"))
    )
    (net (code "29") (name "Net-(Q8-S)") (class "Default")
      (node (ref "Q8") (pin "2") (pinfunction "S_2") (pintype "passive"))
      (node (ref "R5") (pin "1") (pinfunction "1_1") (pintype "passive"))
    )
    (net (code "30") (name "ON{slash}OFF") (class "Default")
      (node (ref "BRICKS1") (pin "05") (pinfunction "ON/OFF_05") (pintype "passive"))
      (node (ref "BRICKS2") (pin "05") (pinfunction "ON/OFF_05") (pintype "passive"))
      (node (ref "D6") (pin "C") (pinfunction "C_C") (pintype "passive"))
      (node (ref "JP1") (pin "2") (pinfunction "2_2") (pintype "passive"))
      (node (ref "ON/OFF_TEST") (pin "1") (pinfunction "1_1") (pintype "passive"))
      (node (ref "Q1") (pin "3") (pinfunction "D_3") (pintype "bidirectional"))
      (node (ref "R3") (pin "1") (pinfunction "1_1") (pintype "passive"))
    )
    (net (code "31") (name "OR_DRIVE_A") (class "Default")
      (node (ref "Q3") (pin "1") (pinfunction "G_1") (pintype "bidirectional"))
      (node (ref "Q5") (pin "1") (pinfunction "G_1") (pintype "passive"))
      (node (ref "U1") (pin "5") (pinfunction "GATE_5") (pintype "passive"))
    )
    (net (code "32") (name "OR_DRIVE_B") (class "Default")
      (node (ref "Q4") (pin "1") (pinfunction "G_1") (pintype "bidirectional"))
      (node (ref "Q7") (pin "1") (pinfunction "G_1") (pintype "passive"))
      (node (ref "U2") (pin "5") (pinfunction "GATE_5") (pintype "passive"))
    )
    (net (code "33") (name "unconnected-(U1-OFF-Pad3)") (class "Default")
      (node (ref "U1") (pin "3") (pinfunction "OFF_3") (pintype "passive"))
    )
    (net (code "34") (name "unconnected-(U2-OFF-Pad3)") (class "Default")
      (node (ref "U2") (pin "3") (pinfunction "OFF_3") (pintype "passive"))
    )
  )
)
